# 3-Peripheral.net
KiCad netlist of a schematic drawn in Altium Designer
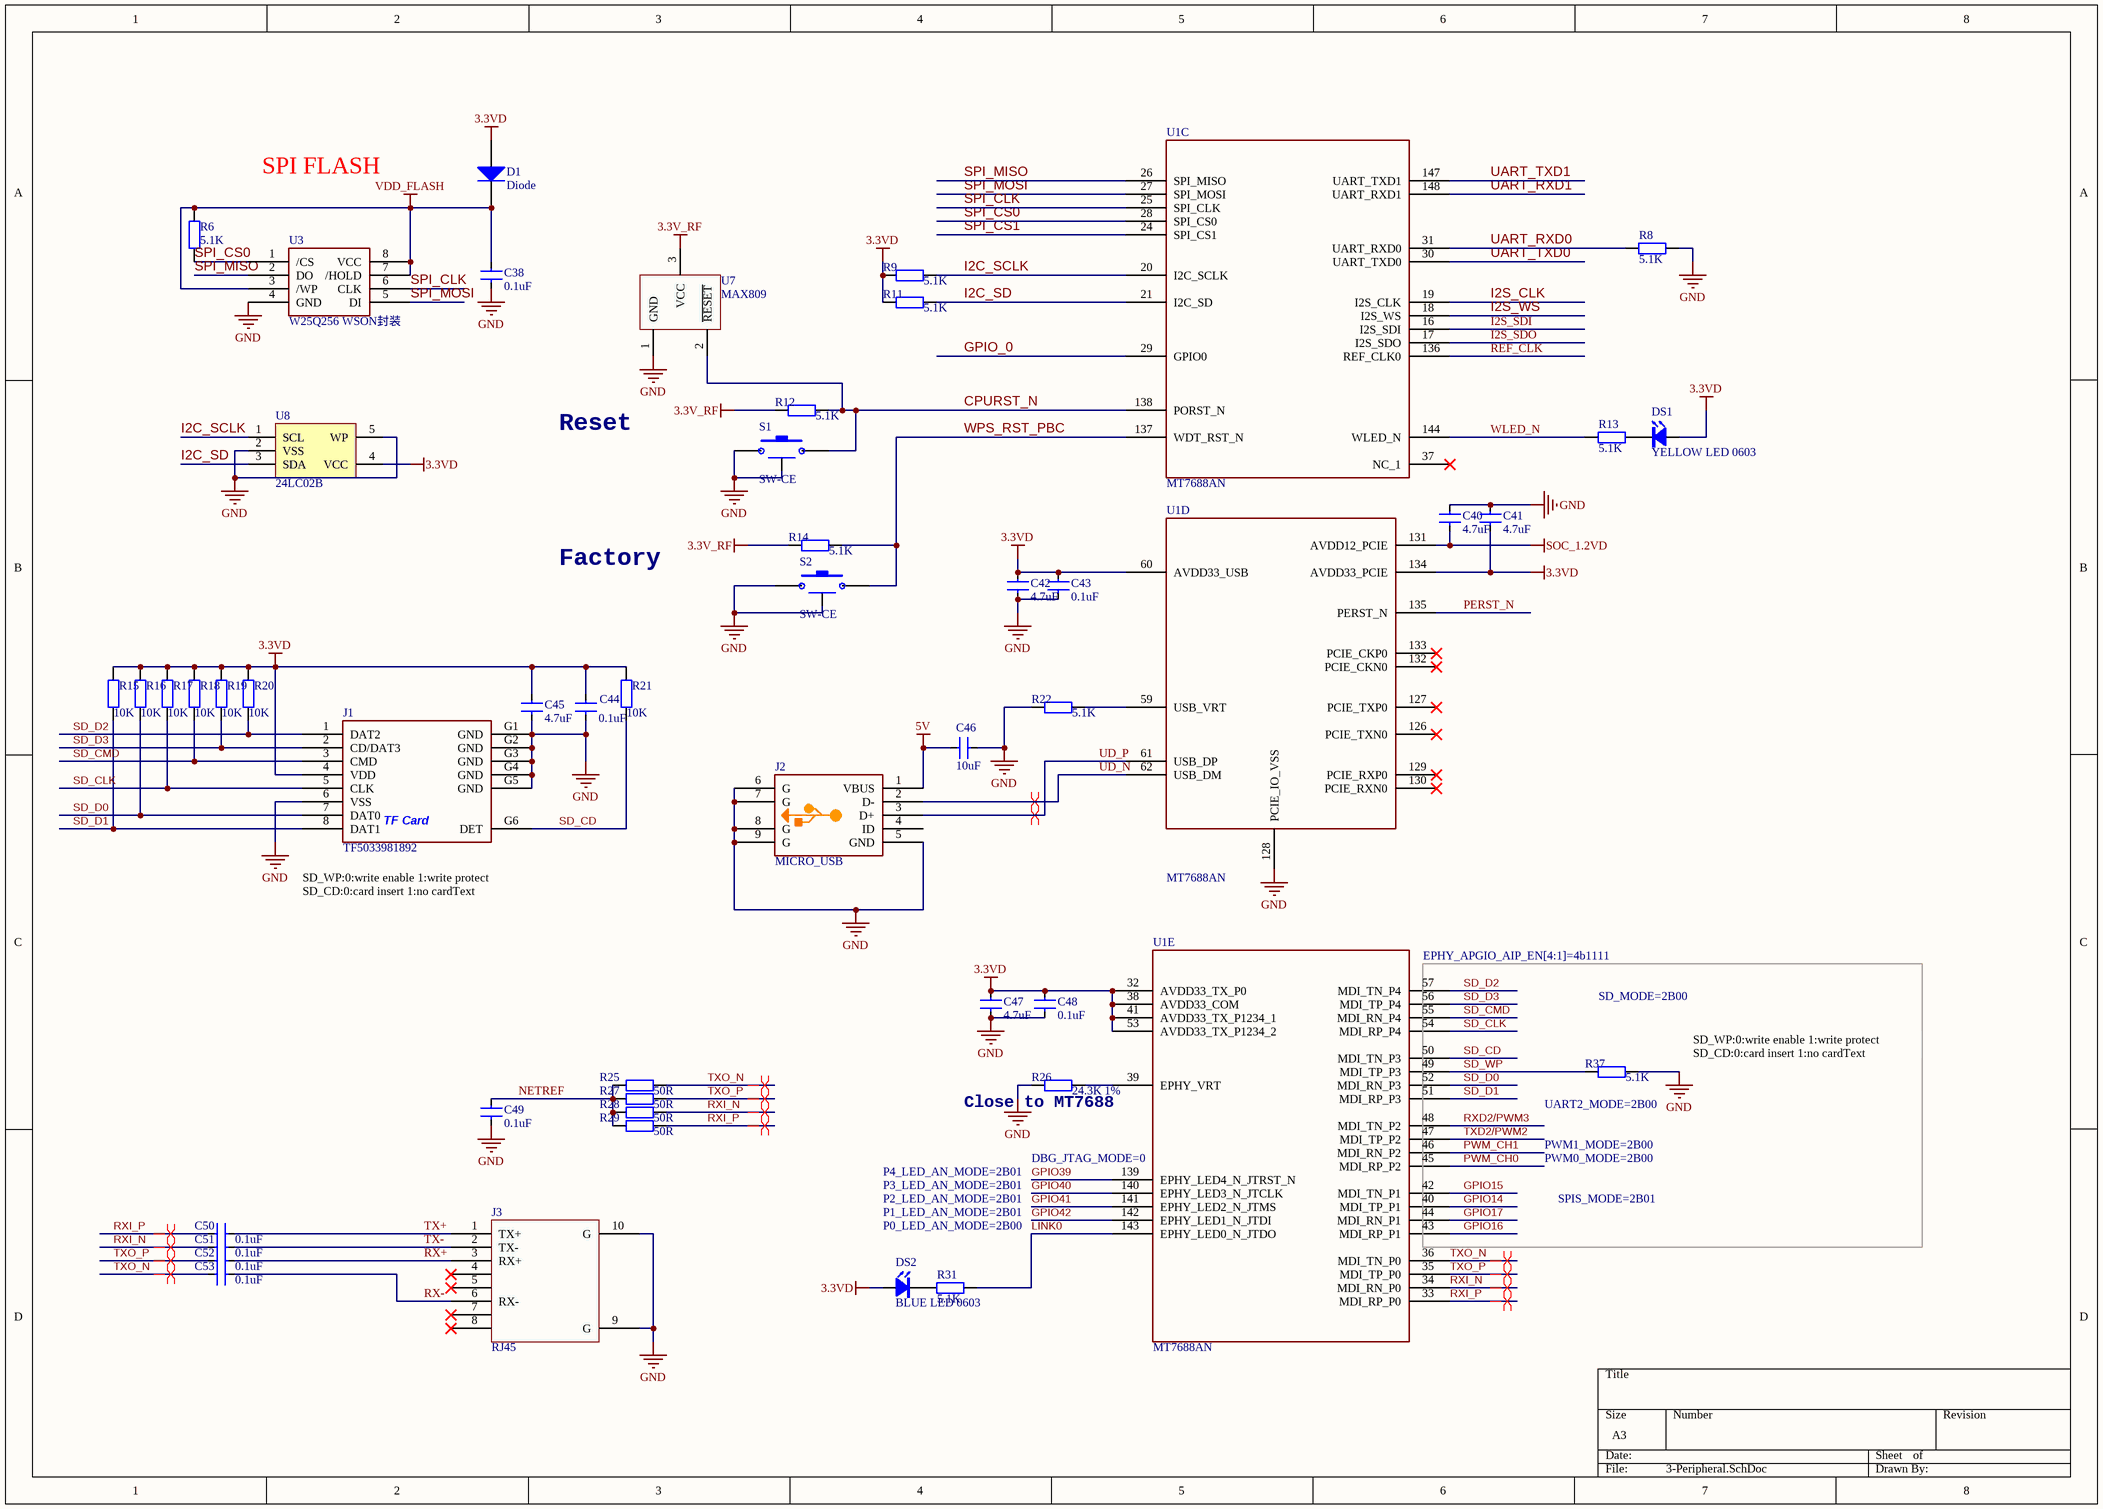
[diagram p0: 3-Peripheral.SchDoc]

(export (version "E")
  (design (tool "Eeschema 10.0.6"))
  (components
    (comp (ref "C38")
      (value "0.1uF")
      (footprint "C0402")
      (description "普通小电容")
      (libsource (lib "LIB_MANGO") (part "CAP"))
    )
    (comp (ref "C40")
      (value "4.7uF")
      (footprint "C0402")
      (description "普通小电容")
      (libsource (lib "LIB_MANGO") (part "CAP"))
    )
    (comp (ref "C41")
      (value "4.7uF")
      (footprint "C0402")
      (description "普通小电容")
      (libsource (lib "LIB_MANGO") (part "CAP"))
    )
    (comp (ref "C42")
      (value "4.7uF")
      (footprint "C0402")
      (description "普通小电容")
      (libsource (lib "LIB_MANGO") (part "CAP"))
    )
    (comp (ref "C43")
      (value "0.1uF")
      (footprint "C0402")
      (description "普通小电容")
      (libsource (lib "LIB_MANGO") (part "CAP"))
    )
    (comp (ref "C44")
      (value "0.1uF")
      (footprint "C0402")
      (description "普通小电容")
      (libsource (lib "LIB_MANGO") (part "CAP"))
    )
    (comp (ref "C45")
      (value "4.7uF")
      (footprint "C0402")
      (description "普通小电容")
      (libsource (lib "LIB_MANGO") (part "CAP"))
    )
    (comp (ref "C46")
      (value "10uF")
      (footprint "0805C")
      (description "普通小电容")
      (libsource (lib "LIB_MANGO") (part "CAP"))
    )
    (comp (ref "C47")
      (value "4.7uF")
      (footprint "C0402")
      (description "普通小电容")
      (libsource (lib "LIB_MANGO") (part "CAP"))
    )
    (comp (ref "C48")
      (value "0.1uF")
      (footprint "C0402")
      (description "普通小电容")
      (libsource (lib "LIB_MANGO") (part "CAP"))
    )
    (comp (ref "C49")
      (value "0.1uF")
      (footprint "C0402")
      (description "普通小电容")
      (libsource (lib "LIB_MANGO") (part "CAP"))
    )
    (comp (ref "C50")
      (value "0.1uF")
      (footprint "C0402")
      (description "普通小电容")
      (libsource (lib "LIB_MANGO") (part "CAP"))
    )
    (comp (ref "C51")
      (value "0.1uF")
      (footprint "C0402")
      (description "普通小电容")
      (libsource (lib "LIB_MANGO") (part "CAP"))
    )
    (comp (ref "C52")
      (value "0.1uF")
      (footprint "C0402")
      (description "普通小电容")
      (libsource (lib "LIB_MANGO") (part "CAP"))
    )
    (comp (ref "C53")
      (value "0.1uF")
      (footprint "C0402")
      (description "普通小电容")
      (libsource (lib "LIB_MANGO") (part "CAP"))
    )
    (comp (ref "D1")
      (value "Diode")
      (footprint "SOD723")
      (description "普通二极管")
      (libsource (lib "LIB_MANGO") (part "Diode"))
    )
    (comp (ref "DS1")
      (value "YELLOW LED 0603")
      (footprint "LED0603")
      (description "黄色0603发光二极管")
      (libsource (lib "") (part "LED_1"))
    )
    (comp (ref "DS2")
      (value "BLUE LED 0603")
      (footprint "LED0603")
      (description "蓝色0603发光二极管")
      (libsource (lib "LIB_MANGO") (part "LED"))
    )
    (comp (ref "J1")
      (value "TF5033981892")
      (footprint "TFCARD")
      (description "Molex TF 卡座")
      (libsource (lib "LIB_MANGO") (part "TF5033981892"))
    )
    (comp (ref "J2")
      (value "MICRO_USB")
      (footprint "MICROUSB")
      (libsource (lib "LIB_MANGO") (part "MICRO_USB"))
    )
    (comp (ref "J3")
      (value "RJ45")
      (footprint "RJ45")
      (description "RJ45不带网络变压器")
      (libsource (lib "LIB_MANGO") (part "RJ45"))
    )
    (comp (ref "R6")
      (value "5.1K")
      (footprint "R0402")
      (description "普通电阻")
      (libsource (lib "LIB_MANGO") (part "RES"))
    )
    (comp (ref "R8")
      (value "5.1K")
      (footprint "R0402")
      (description "普通电阻")
      (libsource (lib "") (part "RES_1"))
    )
    (comp (ref "R9")
      (value "5.1K")
      (footprint "R0402")
      (description "普通电阻")
      (libsource (lib "") (part "RES_1"))
    )
    (comp (ref "R11")
      (value "5.1K")
      (footprint "R0402")
      (description "普通电阻")
      (libsource (lib "") (part "RES_1"))
    )
    (comp (ref "R12")
      (value "5.1K")
      (footprint "R0402")
      (description "普通电阻")
      (libsource (lib "") (part "RES_1"))
    )
    (comp (ref "R13")
      (value "5.1K")
      (footprint "R0402")
      (description "普通电阻")
      (libsource (lib "") (part "RES_1"))
    )
    (comp (ref "R14")
      (value "5.1K")
      (footprint "R0402")
      (description "普通电阻")
      (libsource (lib "") (part "RES_1"))
    )
    (comp (ref "R15")
      (value "10K")
      (footprint "R0402")
      (description "普通电阻")
      (libsource (lib "LIB_MANGO") (part "RES"))
    )
    (comp (ref "R16")
      (value "10K")
      (footprint "R0402")
      (description "普通电阻")
      (libsource (lib "LIB_MANGO") (part "RES"))
    )
    (comp (ref "R17")
      (value "10K")
      (footprint "R0402")
      (description "普通电阻")
      (libsource (lib "LIB_MANGO") (part "RES"))
    )
    (comp (ref "R18")
      (value "10K")
      (footprint "R0402")
      (description "普通电阻")
      (libsource (lib "LIB_MANGO") (part "RES"))
    )
    (comp (ref "R19")
      (value "10K")
      (footprint "R0402")
      (description "普通电阻")
      (libsource (lib "LIB_MANGO") (part "RES"))
    )
    (comp (ref "R20")
      (value "10K")
      (footprint "R0402")
      (description "普通电阻")
      (libsource (lib "LIB_MANGO") (part "RES"))
    )
    (comp (ref "R21")
      (value "10K")
      (footprint "R0402")
      (description "普通电阻")
      (libsource (lib "LIB_MANGO") (part "RES"))
    )
    (comp (ref "R22")
      (value "5.1K")
      (footprint "R0402")
      (description "普通电阻1%精度")
      (libsource (lib "") (part "RES_1"))
    )
    (comp (ref "R25")
      (value "50R")
      (footprint "R0402")
      (description "普通电阻")
      (libsource (lib "") (part "RES_1"))
    )
    (comp (ref "R26")
      (value "24.3K 1%")
      (footprint "R0402")
      (description "普通电阻")
      (libsource (lib "") (part "RES_1"))
    )
    (comp (ref "R27")
      (value "50R")
      (footprint "R0402")
      (description "普通电阻")
      (libsource (lib "") (part "RES_1"))
    )
    (comp (ref "R28")
      (value "50R")
      (footprint "R0402")
      (description "普通电阻")
      (libsource (lib "") (part "RES_1"))
    )
    (comp (ref "R29")
      (value "50R")
      (footprint "R0402")
      (description "普通电阻")
      (libsource (lib "") (part "RES_1"))
    )
    (comp (ref "R31")
      (value "5.1K")
      (footprint "R0402")
      (description "普通电阻")
      (libsource (lib "") (part "RES_2"))
    )
    (comp (ref "R37")
      (value "5.1K")
      (footprint "R0402")
      (description "普通电阻1%精度")
      (libsource (lib "") (part "RES_1"))
    )
    (comp (ref "S1") (value "SW-CE") (footprint "KEY-A06") (libsource (lib "A") (part "SW-CE")))
    (comp (ref "S2") (value "SW-CE") (footprint "KEY-A06") (libsource (lib "A") (part "SW-CE")))
    (comp (ref "U1")
      (value "MT7688AN")
      (footprint "MT7628AN/DRQFN156/SMD/P0.5/12X12")
      (libsource (lib "A") (part "MT7688AN"))
    )
    (comp (ref "U3")
      (value "W25Q256 WSON封装")
      (footprint "WSON-SPIFLASH")
      (description "16MB SPIFLASH")
      (libsource (lib "A") (part "SPIFLASH_SOP8W"))
    )
    (comp (ref "U7")
      (value "MAX809")
      (footprint "SOT23")
      (description "2.93V复位芯片")
      (libsource (lib "LIB_MANGO") (part "MAX809"))
    )
    (comp (ref "U8") (value "24LC02B") (footprint "SOT23-5") (libsource (lib "LIB_MANGO") (part "24LC08B")))
  )
  (nets
    (net (code "1") (name "/CPURST_N") (class "Default")
      (node (ref "R12") (pin "1") (pinfunction "1_1") (pintype "passive"))
      (node (ref "S1") (pin "1") (pinfunction "1_1") (pintype "passive"))
      (node (ref "U1") (pin "138") (pinfunction "PORST_N_138") (pintype "passive"))
      (node (ref "U7") (pin "2") (pinfunction "~{RESET}_2") (pintype "passive"))
    )
    (net (code "2") (name "/GPIO14") (class "Default")
      (node (ref "U1") (pin "40") (pinfunction "MDI_TP_P1_40") (pintype "passive"))
    )
    (net (code "3") (name "/GPIO15") (class "Default")
      (node (ref "U1") (pin "42") (pinfunction "MDI_TN_P1_42") (pintype "passive"))
    )
    (net (code "4") (name "/GPIO16") (class "Default")
      (node (ref "U1") (pin "43") (pinfunction "MDI_RP_P1_43") (pintype "passive"))
    )
    (net (code "5") (name "/GPIO17") (class "Default")
      (node (ref "U1") (pin "44") (pinfunction "MDI_RN_P1_44") (pintype "passive"))
    )
    (net (code "6") (name "/GPIO39") (class "Default")
      (node (ref "U1") (pin "139") (pinfunction "EPHY_LED4_N_JTRST_N_139") (pintype "passive"))
    )
    (net (code "7") (name "/GPIO40") (class "Default")
      (node (ref "U1") (pin "140") (pinfunction "EPHY_LED3_N_JTCLK_140") (pintype "passive"))
    )
    (net (code "8") (name "/GPIO41") (class "Default")
      (node (ref "U1") (pin "141") (pinfunction "EPHY_LED2_N_JTMS_141") (pintype "passive"))
    )
    (net (code "9") (name "/GPIO42") (class "Default")
      (node (ref "U1") (pin "142") (pinfunction "EPHY_LED1_N_JTDI_142") (pintype "passive"))
    )
    (net (code "10") (name "/GPIO_0") (class "Default")
      (node (ref "U1") (pin "29") (pinfunction "GPIO0_29") (pintype "passive"))
    )
    (net (code "11") (name "/I2C_SCLK") (class "Default")
      (node (ref "R9") (pin "1") (pinfunction "1_1") (pintype "passive"))
      (node (ref "U1") (pin "20") (pinfunction "I2C_SCLK_20") (pintype "passive"))
      (node (ref "U8") (pin "1") (pinfunction "SCL_1") (pintype "passive"))
    )
    (net (code "12") (name "/I2C_SD") (class "Default")
      (node (ref "R11") (pin "1") (pinfunction "1_1") (pintype "passive"))
      (node (ref "U1") (pin "21") (pinfunction "I2C_SD_21") (pintype "passive"))
      (node (ref "U8") (pin "3") (pinfunction "SDA_3") (pintype "passive"))
    )
    (net (code "13") (name "/I2S_CLK") (class "Default")
      (node (ref "U1") (pin "19") (pinfunction "I2S_CLK_19") (pintype "passive"))
    )
    (net (code "14") (name "/I2S_SDI") (class "Default")
      (node (ref "U1") (pin "16") (pinfunction "I2S_SDI_16") (pintype "passive"))
    )
    (net (code "15") (name "/I2S_SDO") (class "Default")
      (node (ref "U1") (pin "17") (pinfunction "I2S_SDO_17") (pintype "passive"))
    )
    (net (code "16") (name "/I2S_WS") (class "Default")
      (node (ref "U1") (pin "18") (pinfunction "I2S_WS_18") (pintype "passive"))
    )
    (net (code "17") (name "/LINK0") (class "Default")
      (node (ref "R31") (pin "2") (pinfunction "2_2") (pintype "passive"))
      (node (ref "U1") (pin "143") (pinfunction "EPHY_LED0_N_JTDO_143") (pintype "passive"))
    )
    (net (code "18") (name "/NETREF") (class "Default")
      (node (ref "C49") (pin "2") (pinfunction "2_2") (pintype "passive"))
      (node (ref "R25") (pin "2") (pinfunction "2_2") (pintype "passive"))
      (node (ref "R27") (pin "2") (pinfunction "2_2") (pintype "passive"))
      (node (ref "R28") (pin "2") (pinfunction "2_2") (pintype "passive"))
      (node (ref "R29") (pin "2") (pinfunction "2_2") (pintype "passive"))
    )
    (net (code "19") (name "/PERST_N") (class "Default")
      (node (ref "U1") (pin "135") (pinfunction "PERST_N_135") (pintype "passive"))
    )
    (net (code "20") (name "/PWM_CH0") (class "Default")
      (node (ref "U1") (pin "45") (pinfunction "MDI_RP_P2_45") (pintype "passive"))
    )
    (net (code "21") (name "/PWM_CH1") (class "Default")
      (node (ref "U1") (pin "46") (pinfunction "MDI_RN_P2_46") (pintype "passive"))
    )
    (net (code "22") (name "/REF_CLK") (class "Default")
      (node (ref "U1") (pin "136") (pinfunction "REF_CLK0_136") (pintype "passive"))
    )
    (net (code "23") (name "/RX+") (class "Default")
      (node (ref "C52") (pin "2") (pinfunction "2_2") (pintype "passive"))
      (node (ref "J3") (pin "3") (pinfunction "RX+_3") (pintype "power_in"))
    )
    (net (code "24") (name "/RX-") (class "Default")
      (node (ref "C53") (pin "2") (pinfunction "2_2") (pintype "passive"))
      (node (ref "J3") (pin "6") (pinfunction "RX-_6") (pintype "power_in"))
    )
    (net (code "25") (name "/RXD2{slash}PWM3") (class "Default")
      (node (ref "U1") (pin "48") (pinfunction "MDI_TN_P2_48") (pintype "passive"))
    )
    (net (code "26") (name "/RXI_N") (class "Default")
      (node (ref "C51") (pin "1") (pinfunction "1_1") (pintype "passive"))
      (node (ref "R28") (pin "1") (pinfunction "1_1") (pintype "passive"))
      (node (ref "U1") (pin "34") (pinfunction "MDI_RN_P0_34") (pintype "passive"))
    )
    (net (code "27") (name "/RXI_P") (class "Default")
      (node (ref "C50") (pin "1") (pinfunction "1_1") (pintype "passive"))
      (node (ref "R29") (pin "1") (pinfunction "1_1") (pintype "passive"))
      (node (ref "U1") (pin "33") (pinfunction "MDI_RP_P0_33") (pintype "passive"))
    )
    (net (code "28") (name "/SD_CD") (class "Default")
      (node (ref "J1") (pin "G6") (pinfunction "DET_G6") (pintype "power_in"))
      (node (ref "R21") (pin "2") (pinfunction "2_2") (pintype "passive"))
      (node (ref "U1") (pin "50") (pinfunction "MDI_TN_P3_50") (pintype "passive"))
    )
    (net (code "29") (name "/SD_CLK") (class "Default")
      (node (ref "J1") (pin "5") (pinfunction "CLK_5") (pintype "passive"))
      (node (ref "R17") (pin "2") (pinfunction "2_2") (pintype "passive"))
      (node (ref "U1") (pin "54") (pinfunction "MDI_RP_P4_54") (pintype "passive"))
    )
    (net (code "30") (name "/SD_CMD") (class "Default")
      (node (ref "J1") (pin "3") (pinfunction "CMD_3") (pintype "passive"))
      (node (ref "R18") (pin "2") (pinfunction "2_2") (pintype "passive"))
      (node (ref "U1") (pin "55") (pinfunction "MDI_RN_P4_55") (pintype "passive"))
    )
    (net (code "31") (name "/SD_D0") (class "Default")
      (node (ref "J1") (pin "7") (pinfunction "DAT0_7") (pintype "passive"))
      (node (ref "R16") (pin "2") (pinfunction "2_2") (pintype "passive"))
      (node (ref "U1") (pin "52") (pinfunction "MDI_RN_P3_52") (pintype "passive"))
    )
    (net (code "32") (name "/SD_D1") (class "Default")
      (node (ref "J1") (pin "8") (pinfunction "DAT1_8") (pintype "passive"))
      (node (ref "R15") (pin "2") (pinfunction "2_2") (pintype "passive"))
      (node (ref "U1") (pin "51") (pinfunction "MDI_RP_P3_51") (pintype "passive"))
    )
    (net (code "33") (name "/SD_D2") (class "Default")
      (node (ref "J1") (pin "1") (pinfunction "DAT2_1") (pintype "passive"))
      (node (ref "R20") (pin "2") (pinfunction "2_2") (pintype "passive"))
      (node (ref "U1") (pin "57") (pinfunction "MDI_TN_P4_57") (pintype "passive"))
    )
    (net (code "34") (name "/SD_D3") (class "Default")
      (node (ref "J1") (pin "2") (pinfunction "CD/DAT3_2") (pintype "passive"))
      (node (ref "R19") (pin "2") (pinfunction "2_2") (pintype "passive"))
      (node (ref "U1") (pin "56") (pinfunction "MDI_TP_P4_56") (pintype "passive"))
    )
    (net (code "35") (name "/SD_WP") (class "Default")
      (node (ref "R37") (pin "2") (pinfunction "2_2") (pintype "passive"))
      (node (ref "U1") (pin "49") (pinfunction "MDI_TP_P3_49") (pintype "passive"))
    )
    (net (code "36") (name "/SPI_CLK") (class "Default")
      (node (ref "U1") (pin "25") (pinfunction "SPI_CLK_25") (pintype "passive"))
      (node (ref "U3") (pin "6") (pinfunction "CLK_6") (pintype "passive"))
    )
    (net (code "37") (name "/SPI_CS0") (class "Default")
      (node (ref "R6") (pin "2") (pinfunction "2_2") (pintype "passive"))
      (node (ref "U1") (pin "28") (pinfunction "SPI_CS0_28") (pintype "passive"))
      (node (ref "U3") (pin "1") (pinfunction "/CS_1") (pintype "passive"))
    )
    (net (code "38") (name "/SPI_CS1") (class "Default")
      (node (ref "U1") (pin "24") (pinfunction "SPI_CS1_24") (pintype "passive"))
    )
    (net (code "39") (name "/SPI_MISO") (class "Default")
      (node (ref "U1") (pin "26") (pinfunction "SPI_MISO_26") (pintype "passive"))
      (node (ref "U3") (pin "2") (pinfunction "DO_2") (pintype "passive"))
    )
    (net (code "40") (name "/SPI_MOSI") (class "Default")
      (node (ref "U1") (pin "27") (pinfunction "SPI_MOSI_27") (pintype "passive"))
      (node (ref "U3") (pin "5") (pinfunction "DI_5") (pintype "passive"))
    )
    (net (code "41") (name "/TX+") (class "Default")
      (node (ref "C50") (pin "2") (pinfunction "2_2") (pintype "passive"))
      (node (ref "J3") (pin "1") (pinfunction "TX+_1") (pintype "power_in"))
    )
    (net (code "42") (name "/TX-") (class "Default")
      (node (ref "C51") (pin "2") (pinfunction "2_2") (pintype "passive"))
      (node (ref "J3") (pin "2") (pinfunction "TX-_2") (pintype "power_in"))
    )
    (net (code "43") (name "/TXD2{slash}PWM2") (class "Default")
      (node (ref "U1") (pin "47") (pinfunction "MDI_TP_P2_47") (pintype "passive"))
    )
    (net (code "44") (name "/TXO_N") (class "Default")
      (node (ref "C53") (pin "1") (pinfunction "1_1") (pintype "passive"))
      (node (ref "R25") (pin "1") (pinfunction "1_1") (pintype "passive"))
      (node (ref "U1") (pin "36") (pinfunction "MDI_TN_P0_36") (pintype "passive"))
    )
    (net (code "45") (name "/TXO_P") (class "Default")
      (node (ref "C52") (pin "1") (pinfunction "1_1") (pintype "passive"))
      (node (ref "R27") (pin "1") (pinfunction "1_1") (pintype "passive"))
      (node (ref "U1") (pin "35") (pinfunction "MDI_TP_P0_35") (pintype "passive"))
    )
    (net (code "46") (name "/UART_RXD0") (class "Default")
      (node (ref "R8") (pin "2") (pinfunction "2_2") (pintype "passive"))
      (node (ref "U1") (pin "31") (pinfunction "UART_RXD0_31") (pintype "passive"))
    )
    (net (code "47") (name "/UART_RXD1") (class "Default")
      (node (ref "U1") (pin "148") (pinfunction "UART_RXD1_148") (pintype "passive"))
    )
    (net (code "48") (name "/UART_TXD0") (class "Default")
      (node (ref "U1") (pin "30") (pinfunction "UART_TXD0_30") (pintype "passive"))
    )
    (net (code "49") (name "/UART_TXD1") (class "Default")
      (node (ref "U1") (pin "147") (pinfunction "UART_TXD1_147") (pintype "passive"))
    )
    (net (code "50") (name "/UD_N") (class "Default")
      (node (ref "J2") (pin "2") (pinfunction "D-_2") (pintype "passive"))
      (node (ref "U1") (pin "62") (pinfunction "USB_DM_62") (pintype "passive"))
    )
    (net (code "51") (name "/UD_P") (class "Default")
      (node (ref "J2") (pin "3") (pinfunction "D+_3") (pintype "passive"))
      (node (ref "U1") (pin "61") (pinfunction "USB_DP_61") (pintype "passive"))
    )
    (net (code "52") (name "/WLED_N") (class "Default")
      (node (ref "R13") (pin "2") (pinfunction "2_2") (pintype "passive"))
      (node (ref "U1") (pin "144") (pinfunction "WLED_N_144") (pintype "passive"))
    )
    (net (code "53") (name "/WPS_RST_PBC") (class "Default")
      (node (ref "R14") (pin "1") (pinfunction "1_1") (pintype "passive"))
      (node (ref "S2") (pin "2") (pinfunction "2_2") (pintype "passive"))
      (node (ref "U1") (pin "137") (pinfunction "WDT_RST_N_137") (pintype "passive"))
    )
    (net (code "54") (name "3.3VD") (class "Default")
      (node (ref "C41") (pin "2") (pinfunction "2_2") (pintype "passive"))
      (node (ref "C42") (pin "1") (pinfunction "1_1") (pintype "passive"))
      (node (ref "C43") (pin "1") (pinfunction "1_1") (pintype "passive"))
      (node (ref "C44") (pin "1") (pinfunction "1_1") (pintype "passive"))
      (node (ref "C45") (pin "1") (pinfunction "1_1") (pintype "passive"))
      (node (ref "C47") (pin "1") (pinfunction "1_1") (pintype "passive"))
      (node (ref "C48") (pin "1") (pinfunction "1_1") (pintype "passive"))
      (node (ref "D1") (pin "A") (pinfunction "A_A") (pintype "passive"))
      (node (ref "DS1") (pin "A") (pinfunction "1_A") (pintype "passive"))
      (node (ref "DS2") (pin "A") (pinfunction "1_A") (pintype "passive"))
      (node (ref "J1") (pin "4") (pinfunction "VDD_4") (pintype "power_in"))
      (node (ref "R11") (pin "2") (pinfunction "2_2") (pintype "passive"))
      (node (ref "R15") (pin "1") (pinfunction "1_1") (pintype "passive"))
      (node (ref "R16") (pin "1") (pinfunction "1_1") (pintype "passive"))
      (node (ref "R17") (pin "1") (pinfunction "1_1") (pintype "passive"))
      (node (ref "R18") (pin "1") (pinfunction "1_1") (pintype "passive"))
      (node (ref "R19") (pin "1") (pinfunction "1_1") (pintype "passive"))
      (node (ref "R20") (pin "1") (pinfunction "1_1") (pintype "passive"))
      (node (ref "R21") (pin "1") (pinfunction "1_1") (pintype "passive"))
      (node (ref "R9") (pin "2") (pinfunction "2_2") (pintype "passive"))
      (node (ref "U1") (pin "134") (pinfunction "AVDD33_PCIE_134") (pintype "passive"))
      (node (ref "U1") (pin "32") (pinfunction "AVDD33_TX_P0_32") (pintype "passive"))
      (node (ref "U1") (pin "38") (pinfunction "AVDD33_COM_38") (pintype "passive"))
      (node (ref "U1") (pin "41") (pinfunction "AVDD33_TX_P1234_1_41") (pintype "passive"))
      (node (ref "U1") (pin "53") (pinfunction "AVDD33_TX_P1234_2_53") (pintype "passive"))
      (node (ref "U1") (pin "60") (pinfunction "AVDD33_USB_60") (pintype "passive"))
      (node (ref "U8") (pin "4") (pinfunction "VCC_4") (pintype "passive"))
    )
    (net (code "55") (name "3.3V_RF") (class "Default")
      (node (ref "R12") (pin "2") (pinfunction "2_2") (pintype "passive"))
      (node (ref "R14") (pin "2") (pinfunction "2_2") (pintype "passive"))
      (node (ref "U7") (pin "3") (pinfunction "VCC_3") (pintype "passive"))
    )
    (net (code "56") (name "5V") (class "Default")
      (node (ref "C46") (pin "1") (pinfunction "1_1") (pintype "passive"))
      (node (ref "J2") (pin "1") (pinfunction "VBUS_1") (pintype "power_in"))
    )
    (net (code "57") (name "GND") (class "Default")
      (node (ref "C38") (pin "1") (pinfunction "1_1") (pintype "passive"))
      (node (ref "C40") (pin "1") (pinfunction "1_1") (pintype "passive"))
      (node (ref "C41") (pin "1") (pinfunction "1_1") (pintype "passive"))
      (node (ref "C42") (pin "2") (pinfunction "2_2") (pintype "passive"))
      (node (ref "C43") (pin "2") (pinfunction "2_2") (pintype "passive"))
      (node (ref "C44") (pin "2") (pinfunction "2_2") (pintype "passive"))
      (node (ref "C45") (pin "2") (pinfunction "2_2") (pintype "passive"))
      (node (ref "C46") (pin "2") (pinfunction "2_2") (pintype "passive"))
      (node (ref "C47") (pin "2") (pinfunction "2_2") (pintype "passive"))
      (node (ref "C48") (pin "2") (pinfunction "2_2") (pintype "passive"))
      (node (ref "C49") (pin "1") (pinfunction "1_1") (pintype "passive"))
      (node (ref "J1") (pin "6") (pinfunction "VSS_6") (pintype "power_in"))
      (node (ref "J1") (pin "G1") (pinfunction "GND_G1") (pintype "power_in"))
      (node (ref "J1") (pin "G2") (pinfunction "GND_G2") (pintype "power_in"))
      (node (ref "J1") (pin "G3") (pinfunction "GND_G3") (pintype "power_in"))
      (node (ref "J1") (pin "G4") (pinfunction "GND_G4") (pintype "power_in"))
      (node (ref "J1") (pin "G5") (pinfunction "GND_G5") (pintype "power_in"))
      (node (ref "J2") (pin "5") (pinfunction "GND_5") (pintype "power_in"))
      (node (ref "J2") (pin "6") (pinfunction "G_6") (pintype "passive"))
      (node (ref "J2") (pin "7") (pinfunction "G_7") (pintype "passive"))
      (node (ref "J2") (pin "8") (pinfunction "G_8") (pintype "passive"))
      (node (ref "J2") (pin "9") (pinfunction "G_9") (pintype "passive"))
      (node (ref "J3") (pin "10") (pinfunction "G_10") (pintype "power_in"))
      (node (ref "J3") (pin "9") (pinfunction "G_9") (pintype "power_in"))
      (node (ref "R22") (pin "2") (pinfunction "2_2") (pintype "passive"))
      (node (ref "R26") (pin "2") (pinfunction "2_2") (pintype "passive"))
      (node (ref "R37") (pin "1") (pinfunction "1_1") (pintype "passive"))
      (node (ref "R8") (pin "1") (pinfunction "1_1") (pintype "passive"))
      (node (ref "S1") (pin "0") (pinfunction "0_0") (pintype "power_in"))
      (node (ref "S1") (pin "2") (pinfunction "2_2") (pintype "passive"))
      (node (ref "S2") (pin "0") (pinfunction "0_0") (pintype "power_in"))
      (node (ref "S2") (pin "1") (pinfunction "1_1") (pintype "passive"))
      (node (ref "U1") (pin "128") (pinfunction "PCIE_IO_VSS_128") (pintype "passive"))
      (node (ref "U3") (pin "4") (pinfunction "GND_4") (pintype "passive"))
      (node (ref "U7") (pin "1") (pinfunction "GND_1") (pintype "passive"))
      (node (ref "U8") (pin "2") (pinfunction "VSS_2") (pintype "passive"))
      (node (ref "U8") (pin "5") (pinfunction "WP_5") (pintype "passive"))
    )
    (net (code "58") (name "Net-(DS1-2)") (class "Default")
      (node (ref "DS1") (pin "K") (pinfunction "2_K") (pintype "passive"))
      (node (ref "R13") (pin "1") (pinfunction "1_1") (pintype "passive"))
    )
    (net (code "59") (name "Net-(DS2-2)") (class "Default")
      (node (ref "DS2") (pin "K") (pinfunction "2_K") (pintype "passive"))
      (node (ref "R31") (pin "1") (pinfunction "1_1") (pintype "passive"))
    )
    (net (code "60") (name "Net-(U1D-USB_VRT)") (class "Default")
      (node (ref "R22") (pin "1") (pinfunction "1_1") (pintype "passive"))
      (node (ref "U1") (pin "59") (pinfunction "USB_VRT_59") (pintype "passive"))
    )
    (net (code "61") (name "Net-(U1E-EPHY_VRT)") (class "Default")
      (node (ref "R26") (pin "1") (pinfunction "1_1") (pintype "passive"))
      (node (ref "U1") (pin "39") (pinfunction "EPHY_VRT_39") (pintype "passive"))
    )
    (net (code "62") (name "SOC_1.2VD") (class "Default")
      (node (ref "C40") (pin "2") (pinfunction "2_2") (pintype "passive"))
      (node (ref "U1") (pin "131") (pinfunction "AVDD12_PCIE_131") (pintype "passive"))
    )
    (net (code "63") (name "VDD_FLASH") (class "Default")
      (node (ref "C38") (pin "2") (pinfunction "2_2") (pintype "passive"))
      (node (ref "D1") (pin "K") (pinfunction "K_K") (pintype "passive"))
      (node (ref "R6") (pin "1") (pinfunction "1_1") (pintype "passive"))
      (node (ref "U3") (pin "3") (pinfunction "/WP_3") (pintype "passive"))
      (node (ref "U3") (pin "7") (pinfunction "/HOLD_7") (pintype "passive"))
      (node (ref "U3") (pin "8") (pinfunction "VCC_8") (pintype "passive"))
    )
    (net (code "64") (name "unconnected-(J2-ID-Pad4)") (class "Default")
      (node (ref "J2") (pin "4") (pinfunction "ID_4") (pintype "passive"))
    )
    (net (code "65") (name "unconnected-(J3-Pad4)") (class "Default")
      (node (ref "J3") (pin "4") (pintype "power_in+no_connect"))
    )
    (net (code "66") (name "unconnected-(J3-Pad5)") (class "Default")
      (node (ref "J3") (pin "5") (pintype "power_in+no_connect"))
    )
    (net (code "67") (name "unconnected-(J3-Pad7)") (class "Default")
      (node (ref "J3") (pin "7") (pintype "power_in+no_connect"))
    )
    (net (code "68") (name "unconnected-(J3-Pad8)") (class "Default")
      (node (ref "J3") (pin "8") (pintype "power_in+no_connect"))
    )
    (net (code "69") (name "unconnected-(U1C-NC_1-Pad37)") (class "Default")
      (node (ref "U1") (pin "37") (pinfunction "NC_1_37") (pintype "passive+no_connect"))
    )
    (net (code "70") (name "unconnected-(U1D-PCIE_CKN0-Pad132)") (class "Default")
      (node (ref "U1") (pin "132") (pinfunction "PCIE_CKN0_132") (pintype "passive+no_connect"))
    )
    (net (code "71") (name "unconnected-(U1D-PCIE_CKP0-Pad133)") (class "Default")
      (node (ref "U1") (pin "133") (pinfunction "PCIE_CKP0_133") (pintype "passive+no_connect"))
    )
    (net (code "72") (name "unconnected-(U1D-PCIE_RXN0-Pad130)") (class "Default")
      (node (ref "U1") (pin "130") (pinfunction "PCIE_RXN0_130") (pintype "passive+no_connect"))
    )
    (net (code "73") (name "unconnected-(U1D-PCIE_RXP0-Pad129)") (class "Default")
      (node (ref "U1") (pin "129") (pinfunction "PCIE_RXP0_129") (pintype "passive+no_connect"))
    )
    (net (code "74") (name "unconnected-(U1D-PCIE_TXN0-Pad126)") (class "Default")
      (node (ref "U1") (pin "126") (pinfunction "PCIE_TXN0_126") (pintype "passive+no_connect"))
    )
    (net (code "75") (name "unconnected-(U1D-PCIE_TXP0-Pad127)") (class "Default")
      (node (ref "U1") (pin "127") (pinfunction "PCIE_TXP0_127") (pintype "passive+no_connect"))
    )
  )
)
